# temperatuursmeting.net
KiCad netlist of a schematic drawn in Altium Designer
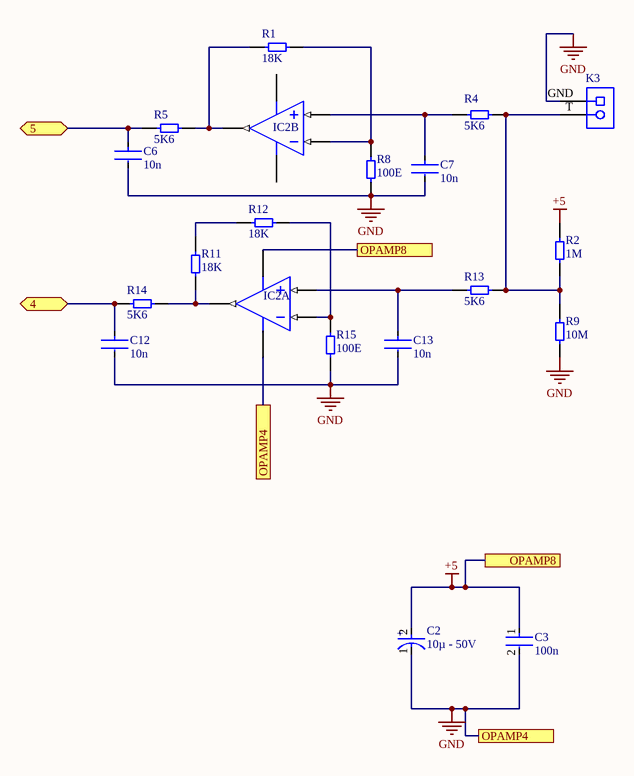
[diagram p0: temperatuursmeting.SchDoc]

(export (version "E")
  (design (tool "Eeschema 10.0.6"))
  (components
    (comp (ref "C2")
      (value "10µ - 50V")
      (footprint "CAPPRD200W52D525H1200")
      (description "Aluminum Electrolytic Capacitors (Radial Lead Type) 100uF ±20% 25V")
      (fields (field (name "TOLERANCE") "20%"))
      (libsource (lib "Soldeerstation") (part "CMP-05427-000897-1"))
    )
    (comp (ref "C3")
      (value "100n")
      (footprint "FP-C0805C-DN-IPC_A")
      (description "CAP CER 0.1UF 50V X7R 0805")
      (fields
        (field (name "MANUFACTURER PART NUMBER") "C0805C104K5RACTU")
        (field (name "MANUFACTURER") "KEMET")
      )
      (libsource (lib "Soldeerstation") (part "CMP-2007-00279-2"))
    )
    (comp (ref "C6")
      (value "10n")
      (footprint "FP-C0805C-DN-IPC_A")
      (description "CAP CER 0.1UF 50V X7R 0805")
      (fields
        (field (name "MANUFACTURER PART NUMBER") "C0805C104K5RACTU")
        (field (name "MANUFACTURER") "KEMET")
      )
      (libsource (lib "") (part "CMP-2007-00279-2_1"))
    )
    (comp (ref "C7")
      (value "10n")
      (footprint "FP-C0805C-DN-IPC_A")
      (description "CAP CER 0.1UF 50V X7R 0805")
      (fields
        (field (name "MANUFACTURER PART NUMBER") "C0805C104K5RACTU")
        (field (name "MANUFACTURER") "KEMET")
      )
      (libsource (lib "") (part "CMP-2007-00279-2_1"))
    )
    (comp (ref "C12")
      (value "10n")
      (footprint "FP-C0805C-DN-IPC_A")
      (description "CAP CER 0.1UF 50V X7R 0805")
      (fields
        (field (name "MANUFACTURER PART NUMBER") "C0805C104K5RACTU")
        (field (name "MANUFACTURER") "KEMET")
      )
      (libsource (lib "") (part "CMP-2007-00279-2_1"))
    )
    (comp (ref "C13")
      (value "10n")
      (footprint "FP-C0805C-DN-IPC_A")
      (description "CAP CER 0.1UF 50V X7R 0805")
      (fields
        (field (name "MANUFACTURER PART NUMBER") "C0805C104K5RACTU")
        (field (name "MANUFACTURER") "KEMET")
      )
      (libsource (lib "") (part "CMP-2007-00279-2_1"))
    )
    (comp (ref "IC2")
      (value "MCP6002-E/P")
      (footprint "PDIP300-P8")
      (description "None")
      (libsource (lib "Soldeerstation") (part "CMP-0187-00133-3"))
    )
    (comp (ref "K3")
      (value "1729128")
      (footprint "PHOE-1729128-2_V")
      (description "PCB Terminal Block, 13.5 A, 400 V, 2-Pin THD, RoHS, Bulk")
      (fields (field (name "MANUFACTURER") "Phoenix Contact"))
      (libsource (lib "Soldeerstation") (part "CMP-2000-05815-1"))
    )
    (comp (ref "R1")
      (value "18K")
      (footprint "RESC2013X60X40ML20T25")
      (fields (field (name "PART NUMBER") "ERA6AEB332V") (field (name "MANUFACTURER") "Panasonic"))
      (libsource (lib "Soldeerstation") (part "CMP-2001-00629-1_1"))
    )
    (comp (ref "R2")
      (value "1M")
      (footprint "RESC2013X60X40ML20T25")
      (fields (field (name "PART NUMBER") "ERA6AEB332V") (field (name "MANUFACTURER") "Panasonic"))
      (libsource (lib "Soldeerstation") (part "CMP-2001-00629-1_1"))
    )
    (comp (ref "R4")
      (value "5K6")
      (footprint "RESC2013X60X40ML20T25")
      (fields (field (name "PART NUMBER") "ERA6AEB332V") (field (name "MANUFACTURER") "Panasonic"))
      (libsource (lib "Soldeerstation") (part "CMP-2001-00629-1_1"))
    )
    (comp (ref "R5")
      (value "5K6")
      (footprint "RESC2013X60X40ML20T25")
      (fields (field (name "PART NUMBER") "ERA6AEB332V") (field (name "MANUFACTURER") "Panasonic"))
      (libsource (lib "Soldeerstation") (part "CMP-2001-00629-1_1"))
    )
    (comp (ref "R8")
      (value "100E")
      (footprint "RESC2013X60X40ML20T25")
      (fields (field (name "PART NUMBER") "ERA6AEB332V") (field (name "MANUFACTURER") "Panasonic"))
      (libsource (lib "Soldeerstation") (part "CMP-2001-00629-1_1"))
    )
    (comp (ref "R9")
      (value "10M")
      (footprint "RESC2013X60X40ML20T25")
      (fields (field (name "PART NUMBER") "ERA6AEB332V") (field (name "MANUFACTURER") "Panasonic"))
      (libsource (lib "Soldeerstation") (part "CMP-2001-00629-1_1"))
    )
    (comp (ref "R11")
      (value "18K")
      (footprint "RESC2013X60X40ML20T25")
      (fields (field (name "PART NUMBER") "ERA6AEB332V") (field (name "MANUFACTURER") "Panasonic"))
      (libsource (lib "Soldeerstation") (part "CMP-2001-00629-1_1"))
    )
    (comp (ref "R12")
      (value "18K")
      (footprint "RESC2013X60X40ML20T25")
      (fields (field (name "PART NUMBER") "ERA6AEB332V") (field (name "MANUFACTURER") "Panasonic"))
      (libsource (lib "Soldeerstation") (part "CMP-2001-00629-1_1"))
    )
    (comp (ref "R13")
      (value "5K6")
      (footprint "RESC2013X60X40ML20T25")
      (fields (field (name "PART NUMBER") "ERA6AEB332V") (field (name "MANUFACTURER") "Panasonic"))
      (libsource (lib "Soldeerstation") (part "CMP-2001-00629-1_1"))
    )
    (comp (ref "R14")
      (value "5K6")
      (footprint "RESC2013X60X40ML20T25")
      (fields (field (name "PART NUMBER") "ERA6AEB332V") (field (name "MANUFACTURER") "Panasonic"))
      (libsource (lib "Soldeerstation") (part "CMP-2001-00629-1_1"))
    )
    (comp (ref "R15")
      (value "100E")
      (footprint "RESC2013X60X40ML20T25")
      (fields (field (name "PART NUMBER") "ERA6AEB332V") (field (name "MANUFACTURER") "Panasonic"))
      (libsource (lib "Soldeerstation") (part "CMP-2001-00629-1_1"))
    )
  )
  (nets
    (net (code "1") (name "+5") (class "Default")
      (node (ref "C2") (pin "2") (pinfunction "A_2") (pintype "passive"))
      (node (ref "C3") (pin "1") (pinfunction "1_1") (pintype "passive"))
      (node (ref "IC2") (pin "4") (pinfunction "VSS_4") (pintype "power_in"))
      (node (ref "R2") (pin "1") (pinfunction "1_1") (pintype "passive"))
    )
    (net (code "2") (name "/4") (class "Default")
      (node (ref "C12") (pin "1") (pinfunction "1_1") (pintype "passive"))
      (node (ref "R14") (pin "1") (pinfunction "1_1") (pintype "passive"))
    )
    (net (code "3") (name "/5") (class "Default")
      (node (ref "C6") (pin "1") (pinfunction "1_1") (pintype "passive"))
      (node (ref "R5") (pin "1") (pinfunction "1_1") (pintype "passive"))
    )
    (net (code "4") (name "GND") (class "Default")
      (node (ref "C12") (pin "2") (pinfunction "2_2") (pintype "passive"))
      (node (ref "C13") (pin "2") (pinfunction "2_2") (pintype "passive"))
      (node (ref "C2") (pin "1") (pinfunction "C_1") (pintype "passive"))
      (node (ref "C3") (pin "2") (pinfunction "2_2") (pintype "passive"))
      (node (ref "C6") (pin "2") (pinfunction "2_2") (pintype "passive"))
      (node (ref "C7") (pin "2") (pinfunction "2_2") (pintype "passive"))
      (node (ref "IC2") (pin "8") (pinfunction "VDD_8") (pintype "power_in"))
      (node (ref "K3") (pin "GND") (pinfunction "1_GND") (pintype "passive"))
      (node (ref "R15") (pin "2") (pinfunction "2_2") (pintype "passive"))
      (node (ref "R8") (pin "2") (pinfunction "2_2") (pintype "passive"))
      (node (ref "R9") (pin "2") (pinfunction "2_2") (pintype "passive"))
    )
    (net (code "5") (name "Net-(IC2A-VINA+)") (class "Default")
      (node (ref "C13") (pin "1") (pinfunction "1_1") (pintype "passive"))
      (node (ref "IC2") (pin "3") (pinfunction "VINA+_3") (pintype "input"))
      (node (ref "R13") (pin "1") (pinfunction "1_1") (pintype "passive"))
    )
    (net (code "6") (name "Net-(IC2A-VINA-)") (class "Default")
      (node (ref "IC2") (pin "2") (pinfunction "VINA-_2") (pintype "input"))
      (node (ref "R12") (pin "2") (pinfunction "2_2") (pintype "passive"))
      (node (ref "R15") (pin "1") (pinfunction "1_1") (pintype "passive"))
    )
    (net (code "7") (name "Net-(IC2A-VOUTA)") (class "Default")
      (node (ref "IC2") (pin "1") (pinfunction "VOUTA_1") (pintype "output"))
      (node (ref "R11") (pin "2") (pinfunction "2_2") (pintype "passive"))
      (node (ref "R14") (pin "2") (pinfunction "2_2") (pintype "passive"))
    )
    (net (code "8") (name "Net-(IC2B-VINB+)") (class "Default")
      (node (ref "C7") (pin "1") (pinfunction "1_1") (pintype "passive"))
      (node (ref "IC2") (pin "5") (pinfunction "VINB+_5") (pintype "input"))
      (node (ref "R4") (pin "1") (pinfunction "1_1") (pintype "passive"))
    )
    (net (code "9") (name "Net-(IC2B-VINB-)") (class "Default")
      (node (ref "IC2") (pin "6") (pinfunction "VINB-_6") (pintype "input"))
      (node (ref "R1") (pin "2") (pinfunction "2_2") (pintype "passive"))
      (node (ref "R8") (pin "1") (pinfunction "1_1") (pintype "passive"))
    )
    (net (code "10") (name "Net-(IC2B-VOUTB)") (class "Default")
      (node (ref "IC2") (pin "7") (pinfunction "VOUTB_7") (pintype "output"))
      (node (ref "R1") (pin "1") (pinfunction "1_1") (pintype "passive"))
      (node (ref "R5") (pin "2") (pinfunction "2_2") (pintype "passive"))
    )
    (net (code "11") (name "Net-(K3-2)") (class "Default")
      (node (ref "K3") (pin "T") (pinfunction "2_T") (pintype "passive"))
      (node (ref "R13") (pin "2") (pinfunction "2_2") (pintype "passive"))
      (node (ref "R2") (pin "2") (pinfunction "2_2") (pintype "passive"))
      (node (ref "R4") (pin "2") (pinfunction "2_2") (pintype "passive"))
      (node (ref "R9") (pin "1") (pinfunction "1_1") (pintype "passive"))
    )
    (net (code "12") (name "Net-(R11-Pad1)") (class "Default")
      (node (ref "R11") (pin "1") (pinfunction "1_1") (pintype "passive"))
      (node (ref "R12") (pin "1") (pinfunction "1_1") (pintype "passive"))
    )
    (net (code "13") (name "unconnected-(IC2B-VDD-Pad8)") (class "Default")
      (node (ref "IC2") (pin "8") (pinfunction "VDD_8") (pintype "power_in"))
    )
    (net (code "14") (name "unconnected-(IC2B-VSS-Pad4)") (class "Default")
      (node (ref "IC2") (pin "4") (pinfunction "VSS_4") (pintype "power_in"))
    )
  )
)
